# 03_-_IMU.net
KiCad netlist of a schematic drawn in Altium Designer
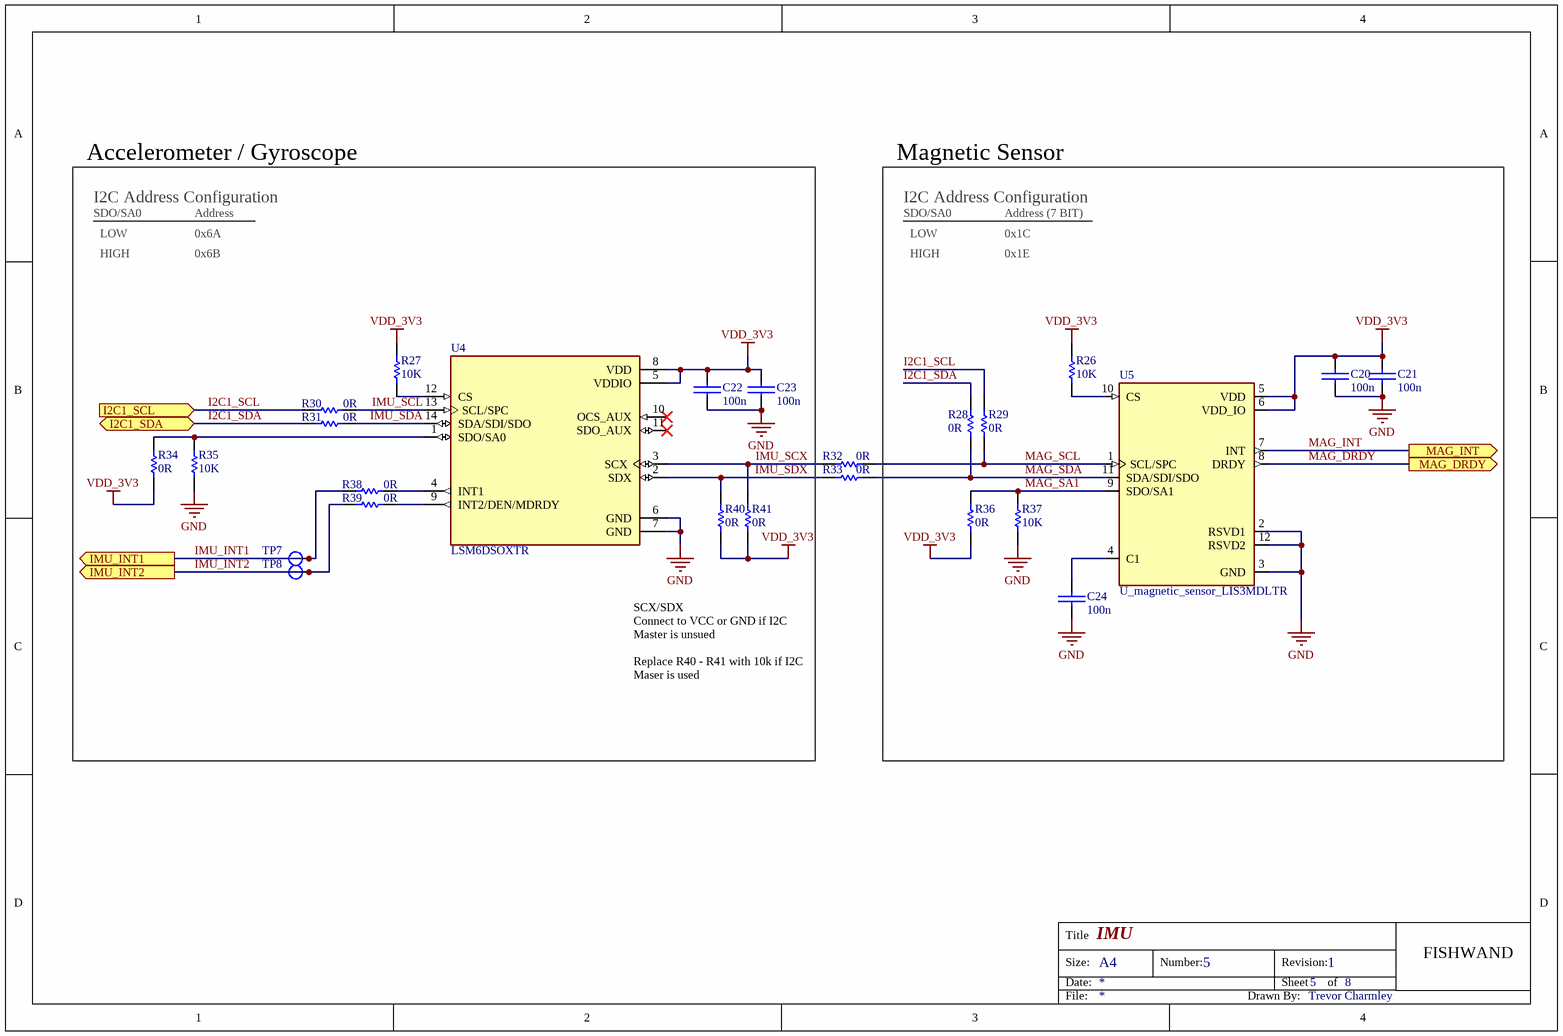
[diagram p0: 03 - IMU.SchDoc]

(export (version "E")
  (design (tool "Eeschema 10.0.6"))
  (components
    (comp (ref "C20")
      (value "100n")
      (footprint "CAPC100X50X65")
      (description "CAP CER 100nF 25V X5R 0402")
      (fields (field (name "MANUFACTURER") "Murata Electronics"))
      (libsource (lib "FishWand_Schlib") (part "C_100NF_25V_X5R_0402"))
    )
    (comp (ref "C21")
      (value "100n")
      (footprint "CAPC100X50X65")
      (description "CAP CER 100nF 25V X5R 0402")
      (fields (field (name "MANUFACTURER") "Murata Electronics"))
      (libsource (lib "FishWand_Schlib") (part "C_100NF_25V_X5R_0402"))
    )
    (comp (ref "C22")
      (value "100n")
      (footprint "CAPC100X50X65")
      (description "CAP CER 100nF 25V X5R 0402")
      (fields (field (name "MANUFACTURER") "Murata Electronics"))
      (libsource (lib "FishWand_Schlib") (part "C_100NF_25V_X5R_0402"))
    )
    (comp (ref "C23")
      (value "100n")
      (footprint "CAPC100X50X65")
      (description "CAP CER 100nF 25V X5R 0402")
      (fields (field (name "MANUFACTURER") "Murata Electronics"))
      (libsource (lib "FishWand_Schlib") (part "C_100NF_25V_X5R_0402"))
    )
    (comp (ref "C24")
      (value "100n")
      (footprint "CAPC100X50X65")
      (description "CAP CER 100nF 25V X5R 0402")
      (fields (field (name "MANUFACTURER") "Murata Electronics"))
      (libsource (lib "FishWand_Schlib") (part "C_100NF_25V_X5R_0402"))
    )
    (comp (ref "R26")
      (value "10K")
      (footprint "RESC0402")
      (description "10 kOhms ±1% 0.063W, 1/16W Chip Resistor 0402 (1005 Metric) Moisture Resistant Thick Film")
      (fields (field (name "MANUFACTURER") "YAGEO") (field (name "TOLERANCE") "1%"))
      (libsource (lib "FishWand_Schlib") (part "R_0402_10K_1%"))
    )
    (comp (ref "R27")
      (value "10K")
      (footprint "RESC0402")
      (description "10 kOhms ±1% 0.063W, 1/16W Chip Resistor 0402 (1005 Metric) Moisture Resistant Thick Film")
      (fields (field (name "MANUFACTURER") "YAGEO") (field (name "TOLERANCE") "1%"))
      (libsource (lib "FishWand_Schlib") (part "R_0402_10K_1%"))
    )
    (comp (ref "R28")
      (value "0R")
      (footprint "RESC0402")
      (description "0 Ohms Jumper 0.063W, 1/16W Chip Resistor 0402 (1005 Metric) Thick Film")
      (fields (field (name "MANUFACTURER") "YAGEO") (field (name "TOLERANCE") "5%"))
      (libsource (lib "FishWand_Schlib") (part "R_0402_0R_5%"))
    )
    (comp (ref "R29")
      (value "0R")
      (footprint "RESC0402")
      (description "0 Ohms Jumper 0.063W, 1/16W Chip Resistor 0402 (1005 Metric) Thick Film")
      (fields (field (name "MANUFACTURER") "YAGEO") (field (name "TOLERANCE") "5%"))
      (libsource (lib "FishWand_Schlib") (part "R_0402_0R_5%"))
    )
    (comp (ref "R30")
      (value "0R")
      (footprint "RESC0402")
      (description "0 Ohms Jumper 0.063W, 1/16W Chip Resistor 0402 (1005 Metric) Thick Film")
      (fields (field (name "MANUFACTURER") "YAGEO") (field (name "TOLERANCE") "5%"))
      (libsource (lib "FishWand_Schlib") (part "R_0402_0R_5%"))
    )
    (comp (ref "R31")
      (value "0R")
      (footprint "RESC0402")
      (description "0 Ohms Jumper 0.063W, 1/16W Chip Resistor 0402 (1005 Metric) Thick Film")
      (fields (field (name "MANUFACTURER") "YAGEO") (field (name "TOLERANCE") "5%"))
      (libsource (lib "FishWand_Schlib") (part "R_0402_0R_5%"))
    )
    (comp (ref "R32")
      (value "0R")
      (footprint "RESC0402")
      (description "0 Ohms Jumper 0.063W, 1/16W Chip Resistor 0402 (1005 Metric) Thick Film")
      (fields (field (name "MANUFACTURER") "YAGEO") (field (name "TOLERANCE") "5%"))
      (libsource (lib "FishWand_Schlib") (part "R_0402_0R_5%"))
    )
    (comp (ref "R33")
      (value "0R")
      (footprint "RESC0402")
      (description "0 Ohms Jumper 0.063W, 1/16W Chip Resistor 0402 (1005 Metric) Thick Film")
      (fields (field (name "MANUFACTURER") "YAGEO") (field (name "TOLERANCE") "5%"))
      (libsource (lib "FishWand_Schlib") (part "R_0402_0R_5%"))
    )
    (comp (ref "R34")
      (value "0R")
      (footprint "RESC0402")
      (description "0 Ohms Jumper 0.063W, 1/16W Chip Resistor 0402 (1005 Metric) Thick Film")
      (fields (field (name "MANUFACTURER") "YAGEO") (field (name "TOLERANCE") "5%"))
      (libsource (lib "FishWand_Schlib") (part "R_0402_0R_5%"))
    )
    (comp (ref "R35")
      (value "10K")
      (footprint "RESC0402")
      (description "10 kOhms ±1% 0.063W, 1/16W Chip Resistor 0402 (1005 Metric) Moisture Resistant Thick Film")
      (fields (field (name "MANUFACTURER") "YAGEO") (field (name "TOLERANCE") "1%"))
      (libsource (lib "FishWand_Schlib") (part "R_0402_10K_1%"))
    )
    (comp (ref "R36")
      (value "0R")
      (footprint "RESC0402")
      (description "0 Ohms Jumper 0.063W, 1/16W Chip Resistor 0402 (1005 Metric) Thick Film")
      (fields (field (name "MANUFACTURER") "YAGEO") (field (name "TOLERANCE") "5%"))
      (libsource (lib "FishWand_Schlib") (part "R_0402_0R_5%"))
    )
    (comp (ref "R37")
      (value "10K")
      (footprint "RESC0402")
      (description "10 kOhms ±1% 0.063W, 1/16W Chip Resistor 0402 (1005 Metric) Moisture Resistant Thick Film")
      (fields (field (name "MANUFACTURER") "YAGEO") (field (name "TOLERANCE") "1%"))
      (libsource (lib "FishWand_Schlib") (part "R_0402_10K_1%"))
    )
    (comp (ref "R38")
      (value "0R")
      (footprint "RESC0402")
      (description "0 Ohms Jumper 0.063W, 1/16W Chip Resistor 0402 (1005 Metric) Thick Film")
      (fields (field (name "MANUFACTURER") "YAGEO") (field (name "TOLERANCE") "5%"))
      (libsource (lib "FishWand_Schlib") (part "R_0402_0R_5%"))
    )
    (comp (ref "R39")
      (value "0R")
      (footprint "RESC0402")
      (description "0 Ohms Jumper 0.063W, 1/16W Chip Resistor 0402 (1005 Metric) Thick Film")
      (fields (field (name "MANUFACTURER") "YAGEO") (field (name "TOLERANCE") "5%"))
      (libsource (lib "FishWand_Schlib") (part "R_0402_0R_5%"))
    )
    (comp (ref "R40")
      (value "0R")
      (footprint "RESC0402")
      (description "0 Ohms Jumper 0.063W, 1/16W Chip Resistor 0402 (1005 Metric) Thick Film")
      (fields (field (name "MANUFACTURER") "YAGEO") (field (name "TOLERANCE") "5%"))
      (libsource (lib "FishWand_Schlib") (part "R_0402_0R_5%"))
    )
    (comp (ref "R41")
      (value "0R")
      (footprint "RESC0402")
      (description "0 Ohms Jumper 0.063W, 1/16W Chip Resistor 0402 (1005 Metric) Thick Film")
      (fields (field (name "MANUFACTURER") "YAGEO") (field (name "TOLERANCE") "5%"))
      (libsource (lib "FishWand_Schlib") (part "R_0402_0R_5%"))
    )
    (comp (ref "TP7")
      (value "Test Point")
      (footprint "tp_1mm")
      (libsource (lib "FishWand_Schlib") (part "TP_1mm"))
    )
    (comp (ref "TP8")
      (value "Test Point")
      (footprint "tp_1mm")
      (libsource (lib "FishWand_Schlib") (part "TP_1mm"))
    )
    (comp (ref "U4")
      (value "LSM6DSOXTR")
      (footprint "FishWand_pcbLib:PQFN50P300X250X86-14N")
      (description "Accelerometer, Gyroscope, Temperature, 6 Axis Sensor IÂ²C, SPI Output")
      (fields (field (name "MANUFACTURER") "STMicroelectronics"))
      (libsource (lib "FishWand_Schlib") (part "U_LSM6DSOXTR"))
    )
    (comp (ref "U5")
      (value "U_magnetic_sensor_LIS3MDLTR")
      (footprint "FishWand_pcbLib:XDCR_LIS3MDLTR")
      (description "Magnetoresistive Sensor X, Y, Z Axis 12-LGA _2x2_")
      (fields (field (name "MANUFACTURER") "STMicroelectronics"))
      (libsource (lib "FishWand_Schlib") (part "U_magnetic_sensor_LIS3MDLTR"))
    )
  )
  (nets
    (net (code "1") (name "/I2C1_SCL") (class "Default")
      (node (ref "R29") (pin "1") (pinfunction "1_1") (pintype "passive"))
      (node (ref "R30") (pin "1") (pinfunction "1_1") (pintype "passive"))
    )
    (net (code "2") (name "/I2C1_SDA") (class "Default")
      (node (ref "R28") (pin "1") (pinfunction "1_1") (pintype "passive"))
      (node (ref "R31") (pin "1") (pinfunction "1_1") (pintype "passive"))
    )
    (net (code "3") (name "/IMU_INT1") (class "Default")
      (node (ref "R38") (pin "1") (pinfunction "1_1") (pintype "passive"))
      (node (ref "TP7") (pin "1") (pinfunction "1_1") (pintype "passive"))
    )
    (net (code "4") (name "/IMU_INT2") (class "Default")
      (node (ref "R39") (pin "1") (pinfunction "1_1") (pintype "passive"))
      (node (ref "TP8") (pin "1") (pinfunction "1_1") (pintype "passive"))
    )
    (net (code "5") (name "/IMU_SCL") (class "Default")
      (node (ref "R30") (pin "2") (pinfunction "2_2") (pintype "passive"))
      (node (ref "U4") (pin "13") (pinfunction "SCL/SPC_13") (pintype "input"))
    )
    (net (code "6") (name "/IMU_SCX") (class "Default")
      (node (ref "R32") (pin "2") (pinfunction "2_2") (pintype "passive"))
      (node (ref "R41") (pin "2") (pinfunction "2_2") (pintype "passive"))
      (node (ref "U4") (pin "3") (pinfunction "SCX_3") (pintype "bidirectional"))
    )
    (net (code "7") (name "/IMU_SDA") (class "Default")
      (node (ref "R31") (pin "2") (pinfunction "2_2") (pintype "passive"))
      (node (ref "U4") (pin "14") (pinfunction "SDA/SDI/SDO_14") (pintype "bidirectional"))
    )
    (net (code "8") (name "/IMU_SDX") (class "Default")
      (node (ref "R33") (pin "2") (pinfunction "2_2") (pintype "passive"))
      (node (ref "R40") (pin "2") (pinfunction "2_2") (pintype "passive"))
      (node (ref "U4") (pin "2") (pinfunction "SDX_2") (pintype "bidirectional"))
    )
    (net (code "9") (name "/MAG_DRDY") (class "Default")
      (node (ref "U5") (pin "8") (pinfunction "DRDY_8") (pintype "output"))
    )
    (net (code "10") (name "/MAG_INT") (class "Default")
      (node (ref "U5") (pin "7") (pinfunction "INT_7") (pintype "output"))
    )
    (net (code "11") (name "/MAG_SA1") (class "Default")
      (node (ref "R36") (pin "2") (pinfunction "2_2") (pintype "passive"))
      (node (ref "R37") (pin "2") (pinfunction "2_2") (pintype "passive"))
      (node (ref "U5") (pin "9") (pinfunction "SDO/SA1_9") (pintype "bidirectional"))
    )
    (net (code "12") (name "/MAG_SCL") (class "Default")
      (node (ref "R29") (pin "2") (pinfunction "2_2") (pintype "passive"))
      (node (ref "R32") (pin "1") (pinfunction "1_1") (pintype "passive"))
      (node (ref "U5") (pin "1") (pinfunction "SCL/SPC_1") (pintype "input"))
    )
    (net (code "13") (name "/MAG_SDA") (class "Default")
      (node (ref "R28") (pin "2") (pinfunction "2_2") (pintype "passive"))
      (node (ref "R33") (pin "1") (pinfunction "1_1") (pintype "passive"))
      (node (ref "U5") (pin "11") (pinfunction "SDA/SDI/SDO_11") (pintype "bidirectional"))
    )
    (net (code "14") (name "GND") (class "Default")
      (node (ref "C20") (pin "2") (pinfunction "2_2") (pintype "passive"))
      (node (ref "C21") (pin "2") (pinfunction "2_2") (pintype "passive"))
      (node (ref "C22") (pin "2") (pinfunction "2_2") (pintype "passive"))
      (node (ref "C23") (pin "2") (pinfunction "2_2") (pintype "passive"))
      (node (ref "C24") (pin "2") (pinfunction "2_2") (pintype "passive"))
      (node (ref "R35") (pin "1") (pinfunction "1_1") (pintype "passive"))
      (node (ref "R37") (pin "1") (pinfunction "1_1") (pintype "passive"))
      (node (ref "U4") (pin "6") (pinfunction "GND_6") (pintype "power_in"))
      (node (ref "U4") (pin "7") (pinfunction "GND_7") (pintype "power_in"))
      (node (ref "U5") (pin "12") (pinfunction "RSVD2_12") (pintype "passive"))
      (node (ref "U5") (pin "2") (pinfunction "RSVD1_2") (pintype "passive"))
      (node (ref "U5") (pin "3") (pinfunction "GND_3") (pintype "power_in"))
    )
    (net (code "15") (name "Net-(U4-CS)") (class "Default")
      (node (ref "R27") (pin "1") (pinfunction "1_1") (pintype "passive"))
      (node (ref "U4") (pin "12") (pinfunction "CS_12") (pintype "input"))
    )
    (net (code "16") (name "Net-(U4-INT1)") (class "Default")
      (node (ref "R38") (pin "2") (pinfunction "2_2") (pintype "passive"))
      (node (ref "U4") (pin "4") (pinfunction "INT1_4") (pintype "output"))
    )
    (net (code "17") (name "Net-(U4-INT2{slash}DEN{slash}MDRDY)") (class "Default")
      (node (ref "R39") (pin "2") (pinfunction "2_2") (pintype "passive"))
      (node (ref "U4") (pin "9") (pinfunction "INT2/DEN/MDRDY_9") (pintype "output"))
    )
    (net (code "18") (name "Net-(U4-SDO{slash}SA0)") (class "Default")
      (node (ref "R34") (pin "2") (pinfunction "2_2") (pintype "passive"))
      (node (ref "R35") (pin "2") (pinfunction "2_2") (pintype "passive"))
      (node (ref "U4") (pin "1") (pinfunction "SDO/SA0_1") (pintype "bidirectional"))
    )
    (net (code "19") (name "Net-(U5-C1)") (class "Default")
      (node (ref "C24") (pin "1") (pinfunction "1_1") (pintype "passive"))
      (node (ref "U5") (pin "4") (pinfunction "C1_4") (pintype "passive"))
    )
    (net (code "20") (name "Net-(U5-CS)") (class "Default")
      (node (ref "R26") (pin "1") (pinfunction "1_1") (pintype "passive"))
      (node (ref "U5") (pin "10") (pinfunction "CS_10") (pintype "input"))
    )
    (net (code "21") (name "VDD_3V3") (class "Default")
      (node (ref "C20") (pin "1") (pinfunction "1_1") (pintype "passive"))
      (node (ref "C21") (pin "1") (pinfunction "1_1") (pintype "passive"))
      (node (ref "C22") (pin "1") (pinfunction "1_1") (pintype "passive"))
      (node (ref "C23") (pin "1") (pinfunction "1_1") (pintype "passive"))
      (node (ref "R26") (pin "2") (pinfunction "2_2") (pintype "passive"))
      (node (ref "R27") (pin "2") (pinfunction "2_2") (pintype "passive"))
      (node (ref "R34") (pin "1") (pinfunction "1_1") (pintype "passive"))
      (node (ref "R36") (pin "1") (pinfunction "1_1") (pintype "passive"))
      (node (ref "R40") (pin "1") (pinfunction "1_1") (pintype "passive"))
      (node (ref "R41") (pin "1") (pinfunction "1_1") (pintype "passive"))
      (node (ref "U4") (pin "5") (pinfunction "VDDIO_5") (pintype "power_in"))
      (node (ref "U4") (pin "8") (pinfunction "VDD_8") (pintype "power_in"))
      (node (ref "U5") (pin "5") (pinfunction "VDD_5") (pintype "power_in"))
      (node (ref "U5") (pin "6") (pinfunction "VDD_IO_6") (pintype "power_in"))
    )
    (net (code "22") (name "unconnected-(U4-OCS_AUX-Pad10)") (class "Default")
      (node (ref "U4") (pin "10") (pinfunction "OCS_AUX_10") (pintype "input+no_connect"))
    )
    (net (code "23") (name "unconnected-(U4-SDO_AUX-Pad11)") (class "Default")
      (node (ref "U4") (pin "11") (pinfunction "SDO_AUX_11") (pintype "bidirectional+no_connect"))
    )
  )
)
